# Misc.net
KiCad netlist of a schematic drawn in Altium Designer
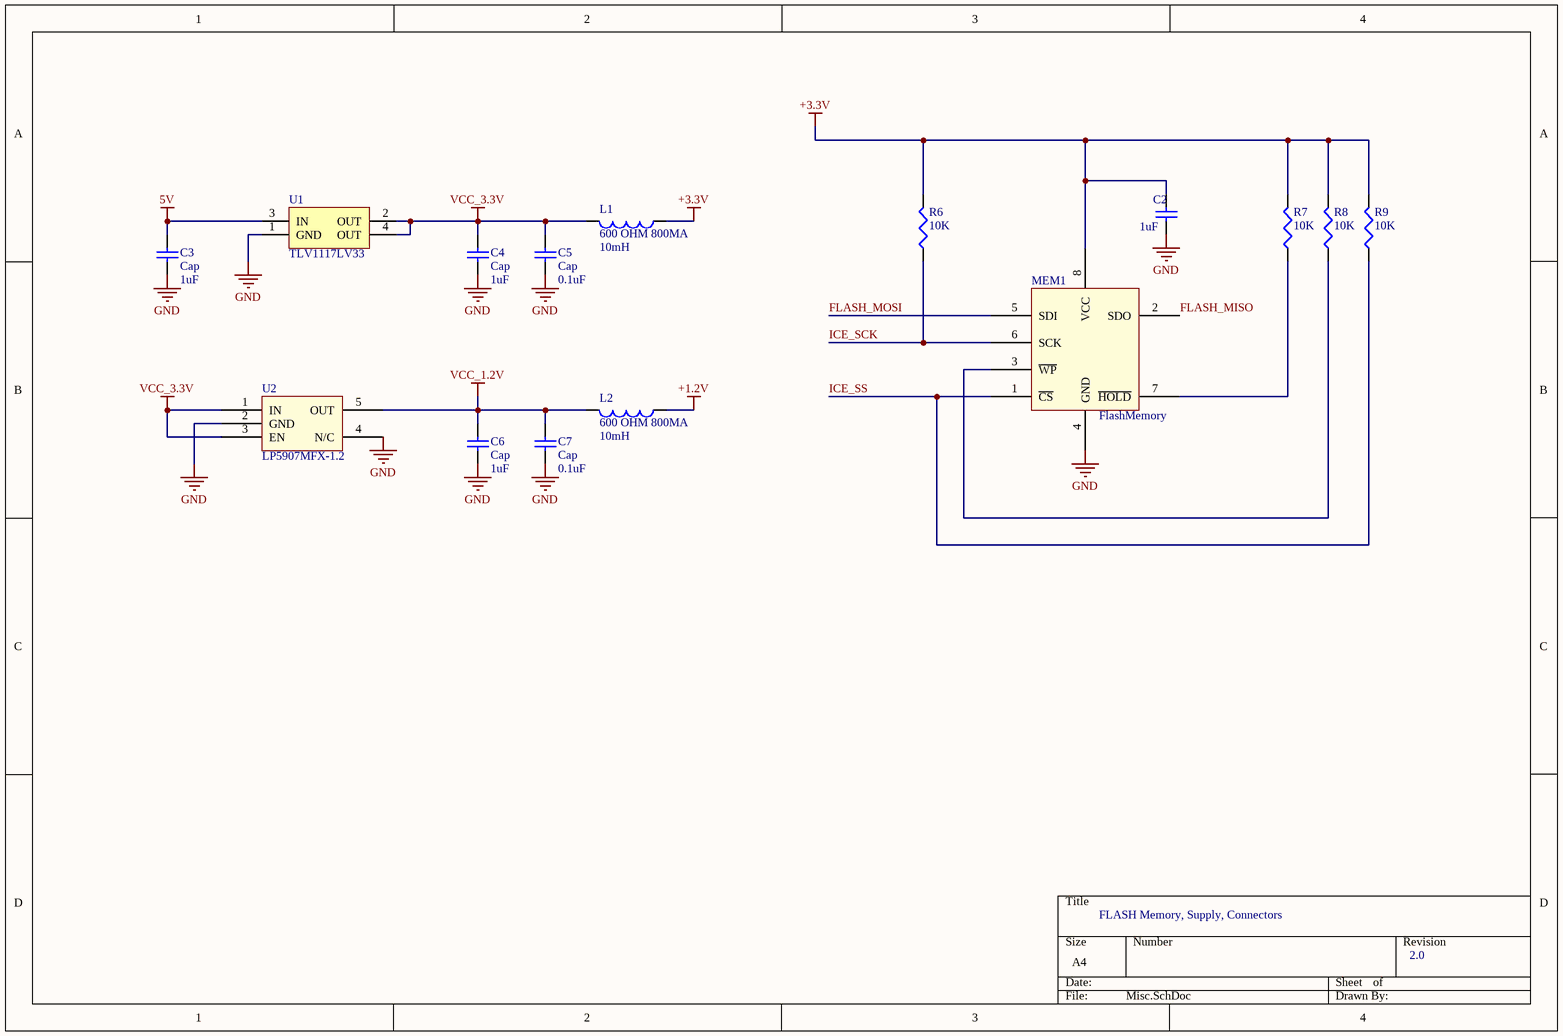
[diagram p0: Misc.SchDoc]

(export (version "E")
  (design (tool "Eeschema 10.0.6"))
  (components
    (comp (ref "C2")
      (value "1uF")
      (footprint "C0402")
      (description "Capacitor (Semiconductor SIM Model)")
      (fields
        (field (name "MANUFACTURER") "TDK Corporation")
        (field (name "MANUFACTURER PART NUMBER") "CGB2A1JB1E105M033BC")
        (field (name "PUBLISHER") "Altium Limited")
      )
      (libsource (lib "Miscellaneous Devices") (part "Cap Semi"))
    )
    (comp (ref "C3")
      (value "Cap")
      (footprint "C0603")
      (description "Capacitor (Semiconductor SIM Model)")
      (fields
        (field (name "ALTIUM_VALUE") "1uF")
        (field (name "MANUFACTURER") "Yageo")
        (field (name "MANUFACTURER PART NUMBER") "CC0603KRX5R8BB105")
        (field (name "PUBLISHER") "Altium Limited")
      )
      (libsource (lib "Miscellaneous Devices") (part "Cap Semi"))
    )
    (comp (ref "C4")
      (value "Cap")
      (footprint "C0603")
      (description "Capacitor (Semiconductor SIM Model)")
      (fields
        (field (name "ALTIUM_VALUE") "1uF")
        (field (name "MANUFACTURER") "Yageo")
        (field (name "MANUFACTURER PART NUMBER") "CC0603KRX5R8BB105")
        (field (name "PUBLISHER") "Altium Limited")
      )
      (libsource (lib "Miscellaneous Devices") (part "Cap Semi"))
    )
    (comp (ref "C5")
      (value "Cap")
      (footprint "C0402")
      (description "Capacitor (Semiconductor SIM Model)")
      (fields
        (field (name "ALTIUM_VALUE") "0.1uF")
        (field (name "MANUFACTURER") "Samsung Electro-Mechanics")
        (field (name "MANUFACTURER PART NUMBER") "CL05B104KA5NNNC")
        (field (name "PUBLISHER") "Altium Limited")
      )
      (libsource (lib "Miscellaneous Devices") (part "Cap Semi"))
    )
    (comp (ref "C6")
      (value "Cap")
      (footprint "C0402")
      (description "Capacitor (Semiconductor SIM Model)")
      (fields
        (field (name "ALTIUM_VALUE") "1uF")
        (field (name "MANUFACTURER") "TDK Corporation")
        (field (name "MANUFACTURER PART NUMBER") "CGB2A1JB1E105M033BC")
        (field (name "PUBLISHER") "Altium Limited")
      )
      (libsource (lib "Miscellaneous Devices") (part "Cap Semi"))
    )
    (comp (ref "C7")
      (value "Cap")
      (footprint "C0402")
      (description "Capacitor (Semiconductor SIM Model)")
      (fields
        (field (name "ALTIUM_VALUE") "0.1uF")
        (field (name "MANUFACTURER") "Samsung Electro-Mechanics")
        (field (name "MANUFACTURER PART NUMBER") "CL05B104KA5NNNC")
        (field (name "PUBLISHER") "Altium Limited")
      )
      (libsource (lib "Miscellaneous Devices") (part "Cap Semi"))
    )
    (comp (ref "L1")
      (value "600 OHM 800MA")
      (footprint "J1-0603")
      (description "Inductor")
      (fields
        (field (name "ALTIUM_VALUE") "10mH")
        (field (name "MANUFACTURER") "Murata Electronics North America")
        (field (name "MANUFACTURER PART NUMBER") "BLM18HE601SN1D")
        (field (name "PUBLISHER") "Altium Limited")
      )
      (libsource (lib "Miscellaneous Devices") (part "Inductor"))
    )
    (comp (ref "L2")
      (value "600 OHM 800MA")
      (footprint "J1-0603")
      (description "Inductor")
      (fields
        (field (name "ALTIUM_VALUE") "10mH")
        (field (name "MANUFACTURER") "Murata Electronics North America")
        (field (name "MANUFACTURER PART NUMBER") "BLM18HE601SN1D")
        (field (name "PUBLISHER") "Altium Limited")
      )
      (libsource (lib "Miscellaneous Devices") (part "Inductor"))
    )
    (comp (ref "MEM1")
      (value "FlashMemory")
      (footprint "SOP8FlashCorrect")
      (description "IC FLASH 32M SPI 133MHZ 8SOIC")
      (fields
        (field (name "MANUFACTURER PART NUMBER") "W25Q32JVSSIQ")
        (field (name "MANUFACTURER") "Winbond Electronics")
      )
      (libsource (lib "FPGAlib") (part "W25Q32JVSSIQ"))
    )
    (comp (ref "R6")
      (value "10K")
      (footprint "R0402")
      (description "Resistor")
      (fields
        (field (name "MANUFACTURER") "Yageo")
        (field (name "MANUFACTURER PART NUMBER") "RC0402JR-0710KP")
        (field (name "PUBLISHER") "Altium Limited")
      )
      (libsource (lib "Miscellaneous Devices") (part "Res3"))
    )
    (comp (ref "R7")
      (value "10K")
      (footprint "R0402")
      (description "Resistor")
      (fields
        (field (name "MANUFACTURER") "Yageo")
        (field (name "MANUFACTURER PART NUMBER") "RC0402JR-0710KP")
        (field (name "PUBLISHER") "Altium Limited")
      )
      (libsource (lib "Miscellaneous Devices") (part "Res3"))
    )
    (comp (ref "R8")
      (value "10K")
      (footprint "R0402")
      (description "Resistor")
      (fields
        (field (name "MANUFACTURER") "Yageo")
        (field (name "MANUFACTURER PART NUMBER") "RC0402JR-0710KP")
        (field (name "PUBLISHER") "Altium Limited")
      )
      (libsource (lib "Miscellaneous Devices") (part "Res3"))
    )
    (comp (ref "R9")
      (value "10K")
      (footprint "R0402")
      (description "Resistor")
      (fields
        (field (name "MANUFACTURER") "Yageo")
        (field (name "MANUFACTURER PART NUMBER") "RC0402JR-0710KP")
        (field (name "PUBLISHER") "Altium Limited")
      )
      (libsource (lib "Miscellaneous Devices") (part "Res3"))
    )
    (comp (ref "U1")
      (value "TLV1117LV33")
      (footprint "ZZ311")
      (description "IC REG LINEAR 3.3V 1A SOT223-4")
      (fields
        (field (name "MANUFACTURER") "Texas Instruments")
        (field (name "MANUFACTURER PART NUMBER") "TLV1117LV33DCYR")
      )
      (libsource (lib "FPGAlib") (part "TLV1117LV33DCYR"))
    )
    (comp (ref "U2")
      (value "LP5907MFX-1.2")
      (footprint "1-2Regulator")
      (description "IC REG LINEAR 1.2V 250MA SOT23-5")
      (fields
        (field (name "MANUFACTURER") "Texas Instruments")
        (field (name "MANUFACTURER PART NUMBER") "LP5907MFX-1.2/NOPB")
      )
      (libsource (lib "FPGAlib") (part "LP5907MFX-1.2/NOPB"))
    )
  )
  (nets
    (net (code "1") (name "+1.2V") (class "Default")
      (node (ref "L2") (pin "1") (pinfunction "1_1") (pintype "passive"))
    )
    (net (code "2") (name "+3.3V") (class "Default")
      (node (ref "C2") (pin "2") (pinfunction "2_2") (pintype "passive"))
      (node (ref "L1") (pin "1") (pinfunction "1_1") (pintype "passive"))
      (node (ref "MEM1") (pin "8") (pinfunction "VCC_8") (pintype "passive"))
      (node (ref "R6") (pin "2") (pinfunction "2_2") (pintype "passive"))
      (node (ref "R7") (pin "2") (pinfunction "2_2") (pintype "passive"))
      (node (ref "R8") (pin "2") (pinfunction "2_2") (pintype "passive"))
      (node (ref "R9") (pin "2") (pinfunction "2_2") (pintype "passive"))
    )
    (net (code "3") (name "/FLASH_MISO") (class "Default")
      (node (ref "MEM1") (pin "2") (pinfunction "SDO_2") (pintype "passive"))
    )
    (net (code "4") (name "/FLASH_MOSI") (class "Default")
      (node (ref "MEM1") (pin "5") (pinfunction "SDI_5") (pintype "passive"))
    )
    (net (code "5") (name "/ICE_SCK") (class "Default")
      (node (ref "MEM1") (pin "6") (pinfunction "SCK_6") (pintype "passive"))
      (node (ref "R6") (pin "1") (pinfunction "1_1") (pintype "passive"))
    )
    (net (code "6") (name "/ICE_SS") (class "Default")
      (node (ref "MEM1") (pin "1") (pinfunction "~{CS}_1") (pintype "passive"))
      (node (ref "R9") (pin "1") (pinfunction "1_1") (pintype "passive"))
    )
    (net (code "7") (name "5V") (class "Default")
      (node (ref "C3") (pin "2") (pinfunction "2_2") (pintype "passive"))
      (node (ref "U1") (pin "3") (pinfunction "IN_3") (pintype "power_in"))
    )
    (net (code "8") (name "GND") (class "Default")
      (node (ref "C2") (pin "1") (pinfunction "1_1") (pintype "passive"))
      (node (ref "C3") (pin "1") (pinfunction "1_1") (pintype "passive"))
      (node (ref "C4") (pin "1") (pinfunction "1_1") (pintype "passive"))
      (node (ref "C5") (pin "1") (pinfunction "1_1") (pintype "passive"))
      (node (ref "C6") (pin "1") (pinfunction "1_1") (pintype "passive"))
      (node (ref "C7") (pin "1") (pinfunction "1_1") (pintype "passive"))
      (node (ref "MEM1") (pin "4") (pinfunction "GND_4") (pintype "passive"))
      (node (ref "U1") (pin "1") (pinfunction "GND_1") (pintype "power_in"))
      (node (ref "U2") (pin "2") (pinfunction "GND_2") (pintype "passive"))
      (node (ref "U2") (pin "4") (pinfunction "N/C_4") (pintype "passive"))
    )
    (net (code "9") (name "Net-(MEM1-~{HOLD})") (class "Default")
      (node (ref "MEM1") (pin "7") (pinfunction "~{HOLD}_7") (pintype "passive"))
      (node (ref "R7") (pin "1") (pinfunction "1_1") (pintype "passive"))
    )
    (net (code "10") (name "Net-(MEM1-~{WP})") (class "Default")
      (node (ref "MEM1") (pin "3") (pinfunction "~{WP}_3") (pintype "passive"))
      (node (ref "R8") (pin "1") (pinfunction "1_1") (pintype "passive"))
    )
    (net (code "11") (name "VCC_1.2V") (class "Default")
      (node (ref "C6") (pin "2") (pinfunction "2_2") (pintype "passive"))
      (node (ref "C7") (pin "2") (pinfunction "2_2") (pintype "passive"))
      (node (ref "L2") (pin "2") (pinfunction "2_2") (pintype "passive"))
      (node (ref "U2") (pin "5") (pinfunction "OUT_5") (pintype "passive"))
    )
    (net (code "12") (name "VCC_3.3V") (class "Default")
      (node (ref "C4") (pin "2") (pinfunction "2_2") (pintype "passive"))
      (node (ref "C5") (pin "2") (pinfunction "2_2") (pintype "passive"))
      (node (ref "L1") (pin "2") (pinfunction "2_2") (pintype "passive"))
      (node (ref "U1") (pin "2") (pinfunction "OUT_2") (pintype "power_in"))
      (node (ref "U1") (pin "4") (pinfunction "OUT_4") (pintype "power_in"))
      (node (ref "U2") (pin "1") (pinfunction "IN_1") (pintype "passive"))
      (node (ref "U2") (pin "3") (pinfunction "EN_3") (pintype "passive"))
    )
  )
)
